# Esquem_tico.net
KiCad netlist of a schematic drawn in EAGLE
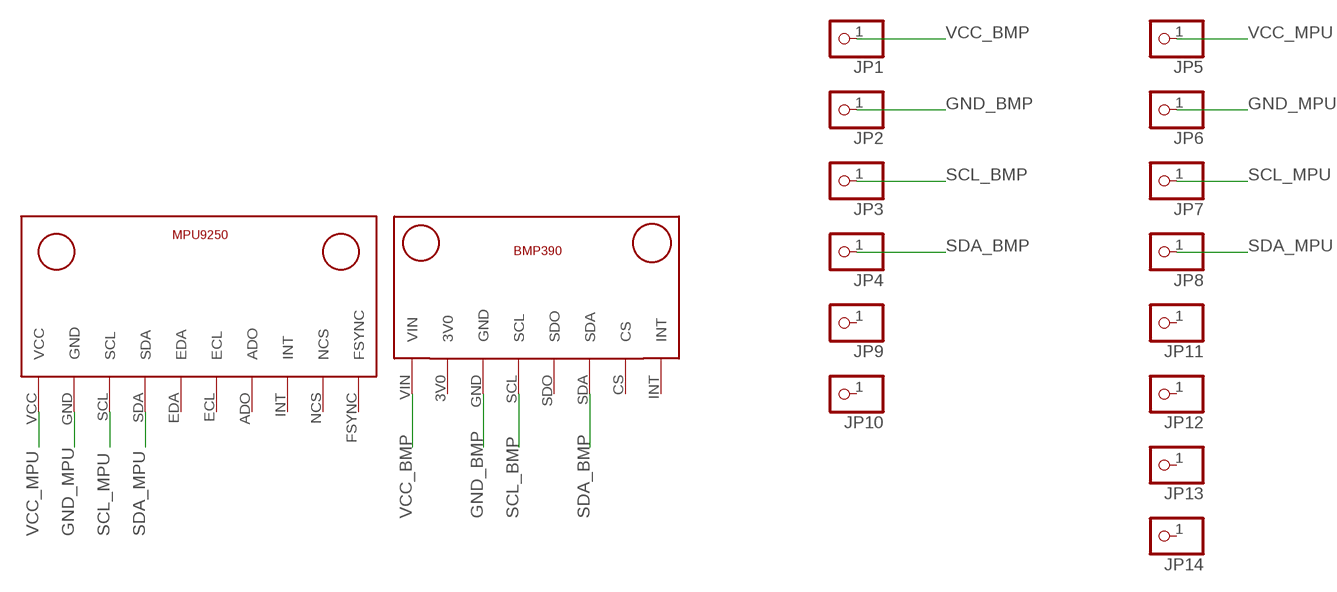
[diagram p0: schematic, sheet 1]

(export (version "E")
  (design (tool "Eeschema 10.0.6"))
  (components
    (comp (ref "JP1")
      (value "PINHD-1X1")
      (footprint "eagle-import:1X01")
      (libsource (lib "eagle-import") (part "PINHD-1X1"))
    )
    (comp (ref "JP2")
      (value "PINHD-1X1")
      (footprint "eagle-import:1X01")
      (libsource (lib "eagle-import") (part "PINHD-1X1"))
    )
    (comp (ref "JP3")
      (value "PINHD-1X1")
      (footprint "eagle-import:1X01")
      (libsource (lib "eagle-import") (part "PINHD-1X1"))
    )
    (comp (ref "JP4")
      (value "PINHD-1X1")
      (footprint "eagle-import:1X01")
      (libsource (lib "eagle-import") (part "PINHD-1X1"))
    )
    (comp (ref "JP5")
      (value "PINHD-1X1")
      (footprint "eagle-import:1X01")
      (libsource (lib "eagle-import") (part "PINHD-1X1"))
    )
    (comp (ref "JP6")
      (value "PINHD-1X1")
      (footprint "eagle-import:1X01")
      (libsource (lib "eagle-import") (part "PINHD-1X1"))
    )
    (comp (ref "JP7")
      (value "PINHD-1X1")
      (footprint "eagle-import:1X01")
      (libsource (lib "eagle-import") (part "PINHD-1X1"))
    )
    (comp (ref "JP8")
      (value "PINHD-1X1")
      (footprint "eagle-import:1X01")
      (libsource (lib "eagle-import") (part "PINHD-1X1"))
    )
    (comp (ref "JP9")
      (value "PINHD-1X1")
      (footprint "eagle-import:1X01")
      (libsource (lib "eagle-import") (part "PINHD-1X1"))
    )
    (comp (ref "JP10")
      (value "PINHD-1X1")
      (footprint "eagle-import:1X01")
      (libsource (lib "eagle-import") (part "PINHD-1X1"))
    )
    (comp (ref "JP11")
      (value "PINHD-1X1")
      (footprint "eagle-import:1X01")
      (libsource (lib "eagle-import") (part "PINHD-1X1"))
    )
    (comp (ref "JP12")
      (value "PINHD-1X1")
      (footprint "eagle-import:1X01")
      (libsource (lib "eagle-import") (part "PINHD-1X1"))
    )
    (comp (ref "JP13")
      (value "PINHD-1X1")
      (footprint "eagle-import:1X01")
      (libsource (lib "eagle-import") (part "PINHD-1X1"))
    )
    (comp (ref "JP14")
      (value "PINHD-1X1")
      (footprint "eagle-import:1X01")
      (libsource (lib "eagle-import") (part "PINHD-1X1"))
    )
    (comp (ref "U$3")
      (value "BMP390V1")
      (footprint "eagle-import:BMP390_FOOTPRINT")
      (libsource (lib "eagle-import") (part "BMP390V1"))
    )
    (comp (ref "U$4")
      (value "MPU9250V1")
      (footprint "eagle-import:MPU9250_FOOTPRINT")
      (libsource (lib "eagle-import") (part "MPU9250V1"))
    )
  )
  (nets
    (net (code "1") (name "/GND_BMP") (class "Default")
      (node (ref "JP2") (pin "1") (pinfunction "1_1") (pintype "passive"))
      (node (ref "U$3") (pin "GND") (pinfunction "GND_GND") (pintype "bidirectional"))
    )
    (net (code "2") (name "/GND_MPU") (class "Default")
      (node (ref "JP6") (pin "1") (pinfunction "1_1") (pintype "passive"))
      (node (ref "U$4") (pin "GND") (pinfunction "GND_GND") (pintype "bidirectional"))
    )
    (net (code "3") (name "/SCL_BMP") (class "Default")
      (node (ref "JP3") (pin "1") (pinfunction "1_1") (pintype "passive"))
      (node (ref "U$3") (pin "SCL") (pinfunction "SCL_SCL") (pintype "bidirectional"))
    )
    (net (code "4") (name "/SCL_MPU") (class "Default")
      (node (ref "JP7") (pin "1") (pinfunction "1_1") (pintype "passive"))
      (node (ref "U$4") (pin "SCL") (pinfunction "SCL_SCL") (pintype "bidirectional"))
    )
    (net (code "5") (name "/SDA_BMP") (class "Default")
      (node (ref "JP4") (pin "1") (pinfunction "1_1") (pintype "passive"))
      (node (ref "U$3") (pin "SDA") (pinfunction "SDA_SDA") (pintype "bidirectional"))
    )
    (net (code "6") (name "/SDA_MPU") (class "Default")
      (node (ref "JP8") (pin "1") (pinfunction "1_1") (pintype "passive"))
      (node (ref "U$4") (pin "SDA") (pinfunction "SDA_SDA") (pintype "bidirectional"))
    )
    (net (code "7") (name "/VCC_BMP") (class "Default")
      (node (ref "JP1") (pin "1") (pinfunction "1_1") (pintype "passive"))
      (node (ref "U$3") (pin "VIN") (pinfunction "VIN_VIN") (pintype "bidirectional"))
    )
    (net (code "8") (name "/VCC_MPU") (class "Default")
      (node (ref "JP5") (pin "1") (pinfunction "1_1") (pintype "passive"))
      (node (ref "U$4") (pin "VCC") (pinfunction "VCC_VCC") (pintype "bidirectional"))
    )
    (net (code "9") (name "unconnected-(JP9-Pad1)") (class "Default")
      (node (ref "JP9") (pin "1") (pinfunction "1_1") (pintype "passive"))
    )
    (net (code "10") (name "unconnected-(JP10-Pad1)") (class "Default")
      (node (ref "JP10") (pin "1") (pinfunction "1_1") (pintype "passive"))
    )
    (net (code "11") (name "unconnected-(JP11-Pad1)") (class "Default")
      (node (ref "JP11") (pin "1") (pinfunction "1_1") (pintype "passive"))
    )
    (net (code "12") (name "unconnected-(JP12-Pad1)") (class "Default")
      (node (ref "JP12") (pin "1") (pinfunction "1_1") (pintype "passive"))
    )
    (net (code "13") (name "unconnected-(JP13-Pad1)") (class "Default")
      (node (ref "JP13") (pin "1") (pinfunction "1_1") (pintype "passive"))
    )
    (net (code "14") (name "unconnected-(JP14-Pad1)") (class "Default")
      (node (ref "JP14") (pin "1") (pinfunction "1_1") (pintype "passive"))
    )
    (net (code "15") (name "unconnected-(U$3-Pad3V0)") (class "Default")
      (node (ref "U$3") (pin "3V0") (pinfunction "3V0_3V0") (pintype "bidirectional"))
    )
    (net (code "16") (name "unconnected-(U$3-PadCS)") (class "Default")
      (node (ref "U$3") (pin "CS") (pinfunction "CS_CS") (pintype "bidirectional"))
    )
    (net (code "17") (name "unconnected-(U$3-PadINT)") (class "Default")
      (node (ref "U$3") (pin "INT") (pinfunction "INT_INT") (pintype "bidirectional"))
    )
    (net (code "18") (name "unconnected-(U$3-PadSDO)") (class "Default")
      (node (ref "U$3") (pin "SDO") (pinfunction "SDO_SDO") (pintype "bidirectional"))
    )
    (net (code "19") (name "unconnected-(U$4-PadADO)") (class "Default")
      (node (ref "U$4") (pin "ADO") (pinfunction "ADO_ADO") (pintype "bidirectional"))
    )
    (net (code "20") (name "unconnected-(U$4-PadECL)") (class "Default")
      (node (ref "U$4") (pin "ECL") (pinfunction "ECL_ECL") (pintype "bidirectional"))
    )
    (net (code "21") (name "unconnected-(U$4-PadEDA)") (class "Default")
      (node (ref "U$4") (pin "EDA") (pinfunction "EDA_EDA") (pintype "bidirectional"))
    )
    (net (code "22") (name "unconnected-(U$4-PadFSYNC)") (class "Default")
      (node (ref "U$4") (pin "FSYNC") (pinfunction "FSYNC_FSYNC") (pintype "bidirectional"))
    )
    (net (code "23") (name "unconnected-(U$4-PadINT)") (class "Default")
      (node (ref "U$4") (pin "INT") (pinfunction "INT_INT") (pintype "bidirectional"))
    )
    (net (code "24") (name "unconnected-(U$4-PadNCS)") (class "Default")
      (node (ref "U$4") (pin "NCS") (pinfunction "NCS_NCS") (pintype "bidirectional"))
    )
  )
)
